# BreakoutBoardSFH.net
KiCad netlist of a schematic drawn in EAGLE
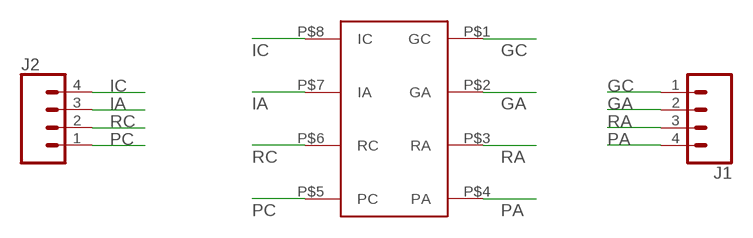
[diagram p0: schematic, sheet 1]

(export (version "E")
  (design (tool "Eeschema 10.0.6"))
  (components
    (comp (ref "J1")
      (value "CONN_04")
      (footprint "eagle-import:1X04")
      (libsource (lib "eagle-import") (part "CONN_04"))
    )
    (comp (ref "J2")
      (value "CONN_04")
      (footprint "eagle-import:1X04")
      (libsource (lib "eagle-import") (part "CONN_04"))
    )
    (comp (ref "U1")
      (value "SFH7050")
      (footprint "eagle-import:SFH7050")
      (libsource (lib "eagle-import") (part "SFH7050"))
    )
  )
  (nets
    (net (code "1") (name "/GA") (class "Default")
      (node (ref "J1") (pin "2") (pinfunction "2_2") (pintype "passive"))
      (node (ref "U1") (pin "P$2") (pinfunction "GA_P$2") (pintype "bidirectional"))
    )
    (net (code "2") (name "/GC") (class "Default")
      (node (ref "J1") (pin "1") (pinfunction "1_1") (pintype "passive"))
      (node (ref "U1") (pin "P$1") (pinfunction "GC_P$1") (pintype "bidirectional"))
    )
    (net (code "3") (name "/IA") (class "Default")
      (node (ref "J2") (pin "3") (pinfunction "3_3") (pintype "passive"))
      (node (ref "U1") (pin "P$7") (pinfunction "IA_P$7") (pintype "bidirectional"))
    )
    (net (code "4") (name "/IC") (class "Default")
      (node (ref "J2") (pin "4") (pinfunction "4_4") (pintype "passive"))
      (node (ref "U1") (pin "P$8") (pinfunction "IC_P$8") (pintype "bidirectional"))
    )
    (net (code "5") (name "/PA") (class "Default")
      (node (ref "J1") (pin "4") (pinfunction "4_4") (pintype "passive"))
      (node (ref "U1") (pin "P$4") (pinfunction "PA_P$4") (pintype "bidirectional"))
    )
    (net (code "6") (name "/PC") (class "Default")
      (node (ref "J2") (pin "1") (pinfunction "1_1") (pintype "passive"))
      (node (ref "U1") (pin "P$5") (pinfunction "PC_P$5") (pintype "bidirectional"))
    )
    (net (code "7") (name "/RA") (class "Default")
      (node (ref "J1") (pin "3") (pinfunction "3_3") (pintype "passive"))
      (node (ref "U1") (pin "P$3") (pinfunction "RA_P$3") (pintype "bidirectional"))
    )
    (net (code "8") (name "/RC") (class "Default")
      (node (ref "J2") (pin "2") (pinfunction "2_2") (pintype "passive"))
      (node (ref "U1") (pin "P$6") (pinfunction "RC_P$6") (pintype "bidirectional"))
    )
  )
)
